# coilcube.net
KiCad netlist of a schematic drawn in EAGLE
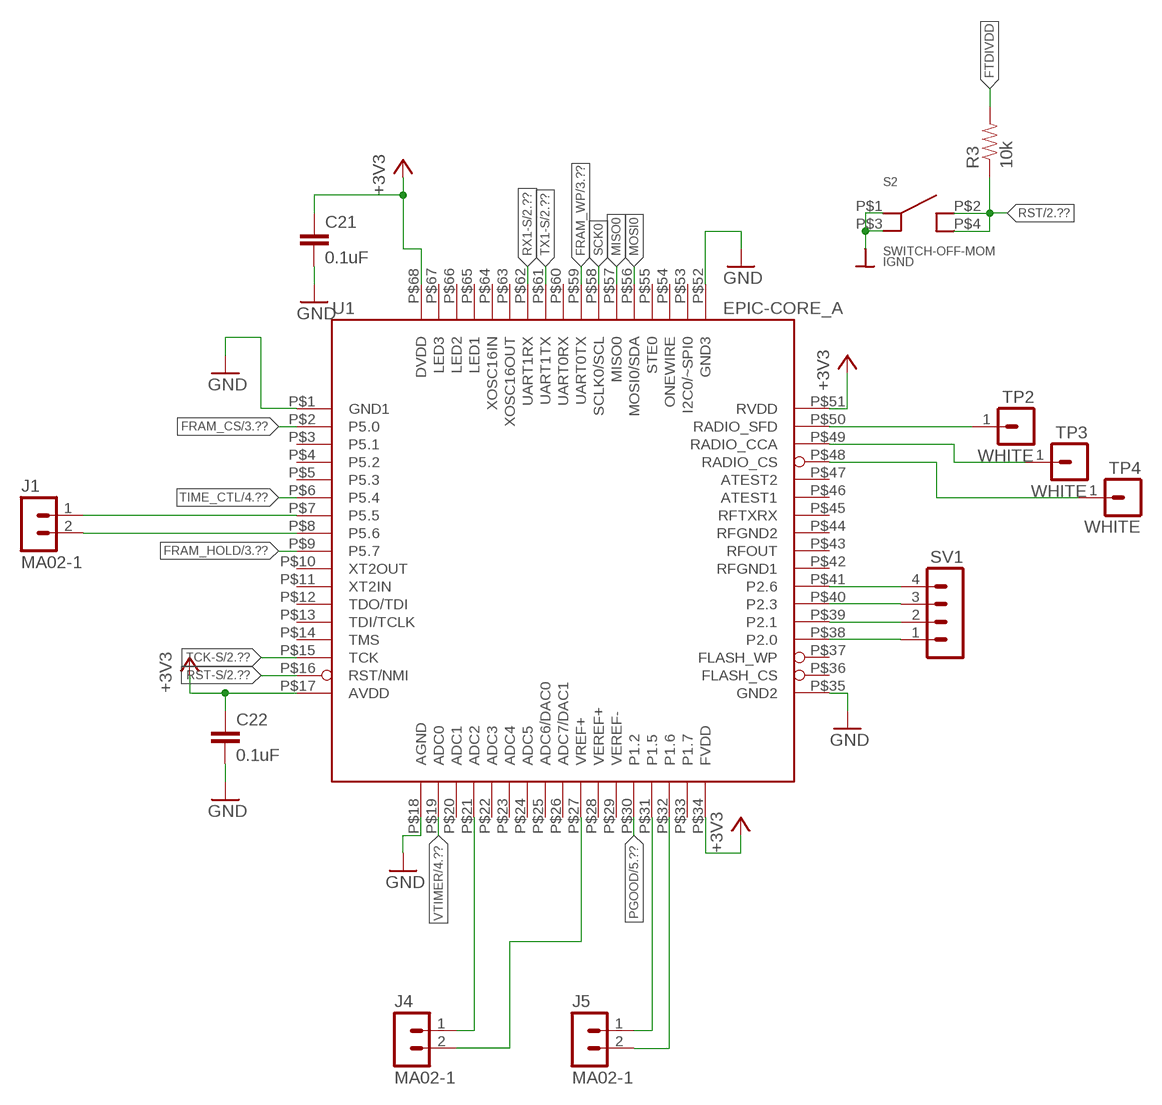
[diagram p0: schematic, sheet 1]
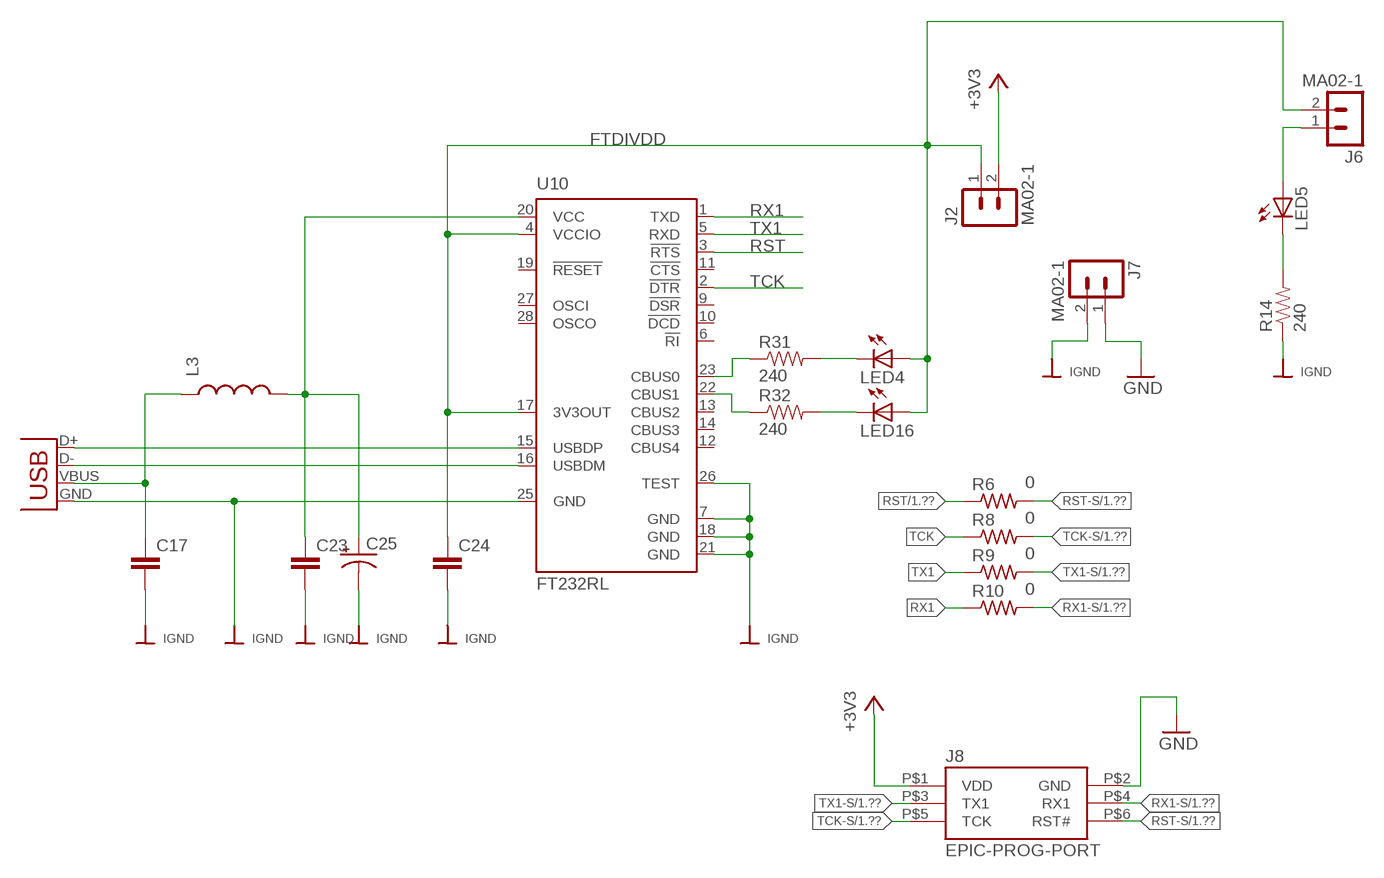
[diagram p1: schematic, sheet 2]
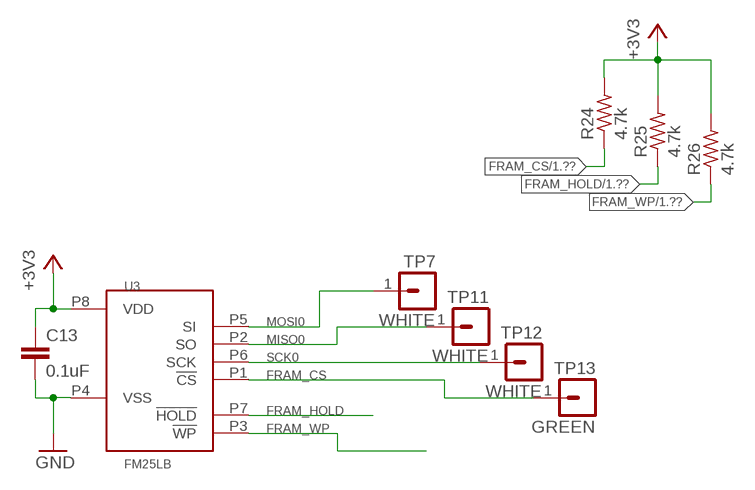
[diagram p2: schematic, sheet 3]
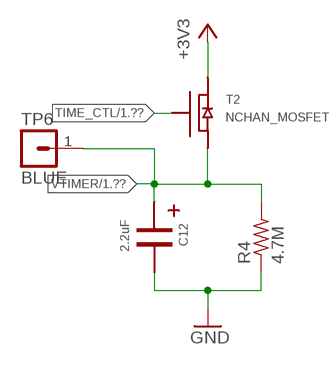
[diagram p3: schematic, sheet 4]
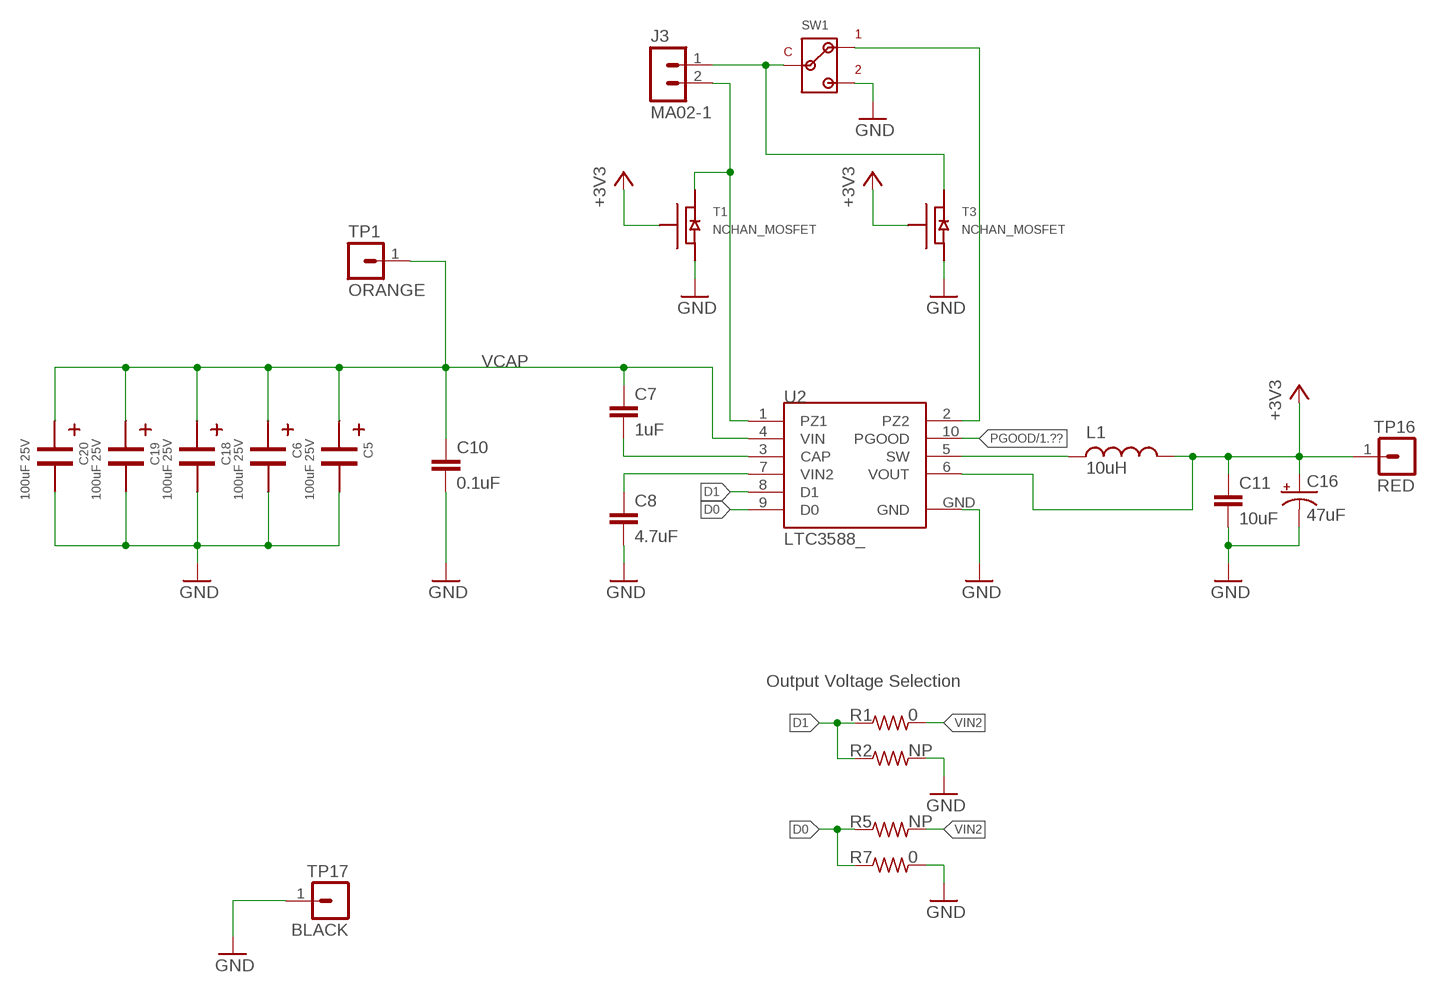
[diagram p4: schematic, sheet 5]

(export (version "E")
  (design (tool "Eeschema 10.0.6"))
  (components
    (comp (ref "C17")
      (value "CAP0603-CAP")
      (footprint "eagle-import:0603-CAP")
      (libsource (lib "eagle-import") (part "CAP0603-CAP"))
    )
    (comp (ref "C23")
      (value "CAP0603-CAP")
      (footprint "eagle-import:0603-CAP")
      (libsource (lib "eagle-import") (part "CAP0603-CAP"))
    )
    (comp (ref "C24")
      (value "CAP0603-CAP")
      (footprint "eagle-import:0603-CAP")
      (libsource (lib "eagle-import") (part "CAP0603-CAP"))
    )
    (comp (ref "C25")
      (value "CAP_POL1206")
      (footprint "eagle-import:EIA3216")
      (libsource (lib "eagle-import") (part "CAP_POL1206"))
    )
    (comp (ref "J2")
      (value "MA02-1")
      (footprint "eagle-import:MA02-1")
      (libsource (lib "eagle-import") (part "MA02-1"))
    )
    (comp (ref "J6")
      (value "MA02-1")
      (footprint "eagle-import:MA02-1")
      (libsource (lib "eagle-import") (part "MA02-1"))
    )
    (comp (ref "J7")
      (value "MA02-1")
      (footprint "eagle-import:MA02-1")
      (libsource (lib "eagle-import") (part "MA02-1"))
    )
    (comp (ref "J8")
      (value "EPIC-PROG-PORT")
      (footprint "eagle-import:HEADER2X3X2MM")
      (libsource (lib "eagle-import") (part "EPIC-PROG-PORT"))
    )
    (comp (ref "L3")
      (value "INDUCTOR0603")
      (footprint "eagle-import:0603")
      (libsource (lib "eagle-import") (part "INDUCTOR0603"))
    )
    (comp (ref "LED4")
      (value "LED0603")
      (footprint "eagle-import:LED-0603")
      (libsource (lib "eagle-import") (part "LED0603"))
    )
    (comp (ref "LED5")
      (value "LED0603")
      (footprint "eagle-import:LED-0603")
      (libsource (lib "eagle-import") (part "LED0603"))
    )
    (comp (ref "LED16")
      (value "LED0603")
      (footprint "eagle-import:LED-0603")
      (libsource (lib "eagle-import") (part "LED0603"))
    )
    (comp (ref "R6")
      (value "0")
      (footprint "eagle-import:R0603")
      (libsource (lib "eagle-import") (part "R-US_R0603"))
    )
    (comp (ref "R8")
      (value "0")
      (footprint "eagle-import:R0603")
      (libsource (lib "eagle-import") (part "R-US_R0603"))
    )
    (comp (ref "R9")
      (value "0")
      (footprint "eagle-import:R0603")
      (libsource (lib "eagle-import") (part "R-US_R0603"))
    )
    (comp (ref "R10")
      (value "0")
      (footprint "eagle-import:R0603")
      (libsource (lib "eagle-import") (part "R-US_R0603"))
    )
    (comp (ref "R14")
      (value "240")
      (footprint "eagle-import:0603-RES")
      (libsource (lib "eagle-import") (part "RESISTOR0603-RES"))
    )
    (comp (ref "R31")
      (value "240")
      (footprint "eagle-import:0603-RES")
      (libsource (lib "eagle-import") (part "RESISTOR0603-RES"))
    )
    (comp (ref "R32")
      (value "240")
      (footprint "eagle-import:0603-RES")
      (libsource (lib "eagle-import") (part "RESISTOR0603-RES"))
    )
    (comp (ref "U10")
      (value "FT232RL")
      (footprint "eagle-import:SSOP28")
      (libsource (lib "eagle-import") (part "FT232RL"))
    )
    (comp (ref "X2")
      (value "USBSMD")
      (footprint "eagle-import:USB-MINIB")
      (libsource (lib "eagle-import") (part "USBSMD"))
    )
    (comp (ref "C5")
      (value "100uF 25V")
      (footprint "eagle-import:2917_CAP_POL")
      (libsource (lib "eagle-import") (part "2917_CAP_POL"))
    )
    (comp (ref "C6")
      (value "100uF 25V")
      (footprint "eagle-import:2917_CAP_POL")
      (libsource (lib "eagle-import") (part "2917_CAP_POL"))
    )
    (comp (ref "C7")
      (value "1uF")
      (footprint "eagle-import:C0603")
      (libsource (lib "eagle-import") (part "C-EUC0603"))
    )
    (comp (ref "C8")
      (value "4.7uF")
      (footprint "eagle-import:C0603")
      (libsource (lib "eagle-import") (part "C-EUC0603"))
    )
    (comp (ref "C10")
      (value "0.1uF")
      (footprint "eagle-import:C0603")
      (libsource (lib "eagle-import") (part "C-EUC0603"))
    )
    (comp (ref "C11")
      (value "10uF")
      (footprint "eagle-import:C1206")
      (libsource (lib "eagle-import") (part "C-EUC1206"))
    )
    (comp (ref "C16")
      (value "47uF")
      (footprint "eagle-import:EIA3216")
      (libsource (lib "eagle-import") (part "SparkFun-Passives_CAP_POL1206"))
    )
    (comp (ref "C18")
      (value "100uF 25V")
      (footprint "eagle-import:2917_CAP_POL")
      (libsource (lib "eagle-import") (part "2917_CAP_POL"))
    )
    (comp (ref "C19")
      (value "100uF 25V")
      (footprint "eagle-import:2917_CAP_POL")
      (libsource (lib "eagle-import") (part "2917_CAP_POL"))
    )
    (comp (ref "C20")
      (value "100uF 25V")
      (footprint "eagle-import:2917_CAP_POL")
      (libsource (lib "eagle-import") (part "2917_CAP_POL"))
    )
    (comp (ref "J3")
      (value "MA02-1")
      (footprint "eagle-import:MA02-1")
      (libsource (lib "eagle-import") (part "MA02-1"))
    )
    (comp (ref "L1")
      (value "10uH")
      (footprint "eagle-import:1210")
      (libsource (lib "eagle-import") (part "SparkFun-Passives_INDUCTOR1210"))
    )
    (comp (ref "R1")
      (value "0")
      (footprint "eagle-import:R0603")
      (libsource (lib "eagle-import") (part "R-US_R0603"))
    )
    (comp (ref "R2")
      (value "NP")
      (footprint "eagle-import:R0603")
      (libsource (lib "eagle-import") (part "R-US_R0603"))
    )
    (comp (ref "R5")
      (value "NP")
      (footprint "eagle-import:R0603")
      (libsource (lib "eagle-import") (part "R-US_R0603"))
    )
    (comp (ref "R7")
      (value "0")
      (footprint "eagle-import:R0603")
      (libsource (lib "eagle-import") (part "R-US_R0603"))
    )
    (comp (ref "SW1")
      (value "SWITCH_SPDP")
      (footprint "eagle-import:SWITCH_SPDP")
      (libsource (lib "eagle-import") (part "SWITCH_SPDP"))
    )
    (comp (ref "T1")
      (value "NCHAN_MOSFET")
      (footprint "eagle-import:NCHAN_MOSFET")
      (libsource (lib "eagle-import") (part "NCHAN_MOSFET"))
    )
    (comp (ref "T3")
      (value "NCHAN_MOSFET")
      (footprint "eagle-import:NCHAN_MOSFET")
      (libsource (lib "eagle-import") (part "NCHAN_MOSFET"))
    )
    (comp (ref "TP1")
      (value "ORANGE")
      (footprint "eagle-import:MA01-1")
      (libsource (lib "eagle-import") (part "MA01-1"))
    )
    (comp (ref "TP16")
      (value "RED")
      (footprint "eagle-import:MA01-1")
      (libsource (lib "eagle-import") (part "MA01-1"))
    )
    (comp (ref "TP17")
      (value "BLACK")
      (footprint "eagle-import:MA01-1")
      (libsource (lib "eagle-import") (part "MA01-1"))
    )
    (comp (ref "U2")
      (value "LTC3588_")
      (footprint "eagle-import:MSOP-10-GNDPAD")
      (libsource (lib "eagle-import") (part "LTC3588_"))
    )
    (comp (ref "C13")
      (value "0.1uF")
      (footprint "eagle-import:C0603")
      (libsource (lib "eagle-import") (part "C-EUC0603"))
    )
    (comp (ref "R24")
      (value "4.7k")
      (footprint "eagle-import:R0603")
      (libsource (lib "eagle-import") (part "R-US_R0603"))
    )
    (comp (ref "R25")
      (value "4.7k")
      (footprint "eagle-import:R0603")
      (libsource (lib "eagle-import") (part "R-US_R0603"))
    )
    (comp (ref "R26")
      (value "4.7k")
      (footprint "eagle-import:R0603")
      (libsource (lib "eagle-import") (part "R-US_R0603"))
    )
    (comp (ref "TP7")
      (value "WHITE")
      (footprint "eagle-import:MA01-1")
      (libsource (lib "eagle-import") (part "MA01-1"))
    )
    (comp (ref "TP11")
      (value "WHITE")
      (footprint "eagle-import:MA01-1")
      (libsource (lib "eagle-import") (part "MA01-1"))
    )
    (comp (ref "TP12")
      (value "WHITE")
      (footprint "eagle-import:MA01-1")
      (libsource (lib "eagle-import") (part "MA01-1"))
    )
    (comp (ref "TP13")
      (value "GREEN")
      (footprint "eagle-import:MA01-1")
      (libsource (lib "eagle-import") (part "MA01-1"))
    )
    (comp (ref "U3")
      (value "FM25LB")
      (footprint "eagle-import:SOIC_8")
      (libsource (lib "eagle-import") (part "FM25LB"))
    )
    (comp (ref "C21")
      (value "0.1uF")
      (footprint "eagle-import:C0603")
      (libsource (lib "eagle-import") (part "C-EUC0603"))
    )
    (comp (ref "C22")
      (value "0.1uF")
      (footprint "eagle-import:C0603")
      (libsource (lib "eagle-import") (part "C-EUC0603"))
    )
    (comp (ref "J1")
      (value "MA02-1")
      (footprint "eagle-import:MA02-1")
      (libsource (lib "eagle-import") (part "MA02-1"))
    )
    (comp (ref "J4")
      (value "MA02-1")
      (footprint "eagle-import:MA02-1")
      (libsource (lib "eagle-import") (part "MA02-1"))
    )
    (comp (ref "J5")
      (value "MA02-1")
      (footprint "eagle-import:MA02-1")
      (libsource (lib "eagle-import") (part "MA02-1"))
    )
    (comp (ref "R3")
      (value "10k")
      (footprint "eagle-import:0603-RES")
      (libsource (lib "eagle-import") (part "RESISTOR0603-RES"))
    )
    (comp (ref "S2")
      (value "SWITCH-OFF-MOM")
      (footprint "eagle-import:SWITCH-OFF-MOM")
      (libsource (lib "eagle-import") (part "SWITCH-OFF-MOM"))
    )
    (comp (ref "SV1")
      (value "MA04-1")
      (footprint "eagle-import:MA04-1")
      (libsource (lib "eagle-import") (part "MA04-1"))
    )
    (comp (ref "TP2")
      (value "WHITE")
      (footprint "eagle-import:MA01-1")
      (libsource (lib "eagle-import") (part "MA01-1"))
    )
    (comp (ref "TP3")
      (value "WHITE")
      (footprint "eagle-import:MA01-1")
      (libsource (lib "eagle-import") (part "MA01-1"))
    )
    (comp (ref "TP4")
      (value "WHITE")
      (footprint "eagle-import:MA01-1")
      (libsource (lib "eagle-import") (part "MA01-1"))
    )
    (comp (ref "U1")
      (value "EPIC-CORE_A")
      (footprint "eagle-import:EPIC-LCC68")
      (libsource (lib "eagle-import") (part "EPIC-CORE_A"))
    )
    (comp (ref "C12")
      (value "2.2uF")
      (footprint "eagle-import:CPOL_EEA_1MM5")
      (libsource (lib "eagle-import") (part "CAP_POLEA1MM5"))
    )
    (comp (ref "R4")
      (value "4.7M")
      (footprint "eagle-import:R0805")
      (libsource (lib "eagle-import") (part "R-US_R0805"))
    )
    (comp (ref "T2")
      (value "NCHAN_MOSFET")
      (footprint "eagle-import:NCHAN_MOSFET")
      (libsource (lib "eagle-import") (part "NCHAN_MOSFET"))
    )
    (comp (ref "TP6")
      (value "BLUE")
      (footprint "eagle-import:MA01-1")
      (libsource (lib "eagle-import") (part "MA01-1"))
    )
  )
  (nets
    (net (code "1") (name "+3V3") (class "Default")
      (node (ref "C11") (pin "1") (pinfunction "1_1") (pintype "passive"))
      (node (ref "C13") (pin "1") (pinfunction "1_1") (pintype "passive"))
      (node (ref "C16") (pin "A") (pinfunction "+_A") (pintype "passive"))
      (node (ref "C21") (pin "1") (pinfunction "1_1") (pintype "passive"))
      (node (ref "C22") (pin "1") (pinfunction "1_1") (pintype "passive"))
      (node (ref "J2") (pin "2") (pinfunction "2_2") (pintype "passive"))
      (node (ref "J8") (pin "P$1") (pinfunction "VDD_P$1") (pintype "bidirectional"))
      (node (ref "L1") (pin "2") (pinfunction "2_2") (pintype "passive"))
      (node (ref "R24") (pin "2") (pinfunction "2_2") (pintype "passive"))
      (node (ref "R25") (pin "2") (pinfunction "2_2") (pintype "passive"))
      (node (ref "R26") (pin "2") (pinfunction "2_2") (pintype "passive"))
      (node (ref "T1") (pin "G") (pinfunction "G_G") (pintype "bidirectional"))
      (node (ref "T2") (pin "D") (pinfunction "D_D") (pintype "bidirectional"))
      (node (ref "T3") (pin "G") (pinfunction "G_G") (pintype "bidirectional"))
      (node (ref "TP16") (pin "1") (pinfunction "1_1") (pintype "passive"))
      (node (ref "U1") (pin "P$17") (pinfunction "AVDD_P$17") (pintype "bidirectional"))
      (node (ref "U1") (pin "P$34") (pinfunction "FVDD_P$34") (pintype "bidirectional"))
      (node (ref "U1") (pin "P$51") (pinfunction "RVDD_P$51") (pintype "bidirectional"))
      (node (ref "U1") (pin "P$68") (pinfunction "DVDD_P$68") (pintype "bidirectional"))
      (node (ref "U2") (pin "6") (pinfunction "VOUT_6") (pintype "bidirectional"))
      (node (ref "U3") (pin "P8") (pinfunction "VDD_P8") (pintype "bidirectional"))
    )
    (net (code "2") (name "D0") (class "Default")
      (node (ref "R5") (pin "1") (pinfunction "1_1") (pintype "passive"))
      (node (ref "R7") (pin "1") (pinfunction "1_1") (pintype "passive"))
      (node (ref "U2") (pin "9") (pinfunction "D0_9") (pintype "bidirectional"))
    )
    (net (code "3") (name "D1") (class "Default")
      (node (ref "R1") (pin "1") (pinfunction "1_1") (pintype "passive"))
      (node (ref "R2") (pin "1") (pinfunction "1_1") (pintype "passive"))
      (node (ref "U2") (pin "8") (pinfunction "D1_8") (pintype "bidirectional"))
    )
    (net (code "4") (name "FRAM_CS") (class "Default")
      (node (ref "R24") (pin "1") (pinfunction "1_1") (pintype "passive"))
      (node (ref "TP13") (pin "1") (pinfunction "1_1") (pintype "passive"))
      (node (ref "U1") (pin "P$2") (pinfunction "P5.0_P$2") (pintype "bidirectional"))
      (node (ref "U3") (pin "P1") (pinfunction "~{CS}_P1") (pintype "bidirectional"))
    )
    (net (code "5") (name "FRAM_HOLD") (class "Default")
      (node (ref "R25") (pin "1") (pinfunction "1_1") (pintype "passive"))
      (node (ref "U1") (pin "P$9") (pinfunction "P5.7_P$9") (pintype "bidirectional"))
      (node (ref "U3") (pin "P7") (pinfunction "~{HOLD}_P7") (pintype "bidirectional"))
    )
    (net (code "6") (name "FRAM_WP") (class "Default")
      (node (ref "R26") (pin "1") (pinfunction "1_1") (pintype "passive"))
      (node (ref "U1") (pin "P$59") (pinfunction "UART0TX_P$59") (pintype "bidirectional"))
      (node (ref "U3") (pin "P3") (pinfunction "~{WP}_P3") (pintype "bidirectional"))
    )
    (net (code "7") (name "FTDIVDD") (class "Default")
      (node (ref "C24") (pin "1") (pinfunction "1_1") (pintype "passive"))
      (node (ref "J2") (pin "1") (pinfunction "1_1") (pintype "passive"))
      (node (ref "J6") (pin "2") (pinfunction "2_2") (pintype "passive"))
      (node (ref "LED16") (pin "A") (pinfunction "A_A") (pintype "passive"))
      (node (ref "LED4") (pin "A") (pinfunction "A_A") (pintype "passive"))
      (node (ref "R3") (pin "2") (pinfunction "2_2") (pintype "passive"))
      (node (ref "U10") (pin "17") (pinfunction "3V3OUT_17") (pintype "output"))
      (node (ref "U10") (pin "4") (pinfunction "VCCIO_4") (pintype "power_in"))
    )
    (net (code "8") (name "GND") (class "Default")
      (node (ref "C10") (pin "2") (pinfunction "2_2") (pintype "passive"))
      (node (ref "C11") (pin "2") (pinfunction "2_2") (pintype "passive"))
      (node (ref "C12") (pin "-") (pinfunction "-_-") (pintype "bidirectional"))
      (node (ref "C13") (pin "2") (pinfunction "2_2") (pintype "passive"))
      (node (ref "C16") (pin "C") (pinfunction "-_C") (pintype "passive"))
      (node (ref "C18") (pin "-") (pinfunction "-_-") (pintype "bidirectional"))
      (node (ref "C19") (pin "-") (pinfunction "-_-") (pintype "bidirectional"))
      (node (ref "C20") (pin "-") (pinfunction "-_-") (pintype "bidirectional"))
      (node (ref "C21") (pin "2") (pinfunction "2_2") (pintype "passive"))
      (node (ref "C22") (pin "2") (pinfunction "2_2") (pintype "passive"))
      (node (ref "C5") (pin "-") (pinfunction "-_-") (pintype "bidirectional"))
      (node (ref "C6") (pin "-") (pinfunction "-_-") (pintype "bidirectional"))
      (node (ref "C8") (pin "2") (pinfunction "2_2") (pintype "passive"))
      (node (ref "J7") (pin "1") (pinfunction "1_1") (pintype "passive"))
      (node (ref "J8") (pin "P$2") (pinfunction "GND_P$2") (pintype "bidirectional"))
      (node (ref "R2") (pin "2") (pinfunction "2_2") (pintype "passive"))
      (node (ref "R4") (pin "1") (pinfunction "1_1") (pintype "passive"))
      (node (ref "R7") (pin "2") (pinfunction "2_2") (pintype "passive"))
      (node (ref "SW1") (pin "P3") (pinfunction "P2_P3") (pintype "bidirectional"))
      (node (ref "T1") (pin "S") (pinfunction "S_S") (pintype "bidirectional"))
      (node (ref "T3") (pin "S") (pinfunction "S_S") (pintype "bidirectional"))
      (node (ref "TP17") (pin "1") (pinfunction "1_1") (pintype "passive"))
      (node (ref "U1") (pin "P$1") (pinfunction "GND1_P$1") (pintype "bidirectional"))
      (node (ref "U1") (pin "P$18") (pinfunction "AGND_P$18") (pintype "bidirectional"))
      (node (ref "U1") (pin "P$35") (pinfunction "GND2_P$35") (pintype "bidirectional"))
      (node (ref "U1") (pin "P$52") (pinfunction "GND3_P$52") (pintype "bidirectional"))
      (node (ref "U2") (pin "GND") (pinfunction "GND_GND") (pintype "bidirectional"))
      (node (ref "U3") (pin "P4") (pinfunction "VSS_P4") (pintype "bidirectional"))
    )
    (net (code "9") (name "IGND") (class "Default")
      (node (ref "C17") (pin "2") (pinfunction "2_2") (pintype "passive"))
      (node (ref "C23") (pin "2") (pinfunction "2_2") (pintype "passive"))
      (node (ref "C24") (pin "2") (pinfunction "2_2") (pintype "passive"))
      (node (ref "C25") (pin "C") (pinfunction "-_C") (pintype "passive"))
      (node (ref "J7") (pin "2") (pinfunction "2_2") (pintype "passive"))
      (node (ref "R14") (pin "1") (pinfunction "1_1") (pintype "passive"))
      (node (ref "S2") (pin "P$1") (pinfunction "P1_P$1") (pintype "bidirectional"))
      (node (ref "S2") (pin "P$3") (pinfunction "P3_P$3") (pintype "bidirectional"))
      (node (ref "U10") (pin "18") (pinfunction "GND_18") (pintype "power_in"))
      (node (ref "U10") (pin "21") (pinfunction "GND_21") (pintype "power_in"))
      (node (ref "U10") (pin "25") (pinfunction "GND_25") (pintype "power_in"))
      (node (ref "U10") (pin "26") (pinfunction "TEST_26") (pintype "input"))
      (node (ref "U10") (pin "7") (pinfunction "GND_7") (pintype "power_in"))
      (node (ref "X2") (pin "GND") (pinfunction "GND_GND") (pintype "bidirectional"))
    )
    (net (code "10") (name "MISO0") (class "Default")
      (node (ref "TP11") (pin "1") (pinfunction "1_1") (pintype "passive"))
      (node (ref "U1") (pin "P$57") (pinfunction "MISO0_P$57") (pintype "bidirectional"))
      (node (ref "U3") (pin "P2") (pinfunction "SO_P2") (pintype "bidirectional"))
    )
    (net (code "11") (name "MOSI0") (class "Default")
      (node (ref "TP7") (pin "1") (pinfunction "1_1") (pintype "passive"))
      (node (ref "U1") (pin "P$56") (pinfunction "MOSI0/SDA_P$56") (pintype "bidirectional"))
      (node (ref "U3") (pin "P5") (pinfunction "SI_P5") (pintype "bidirectional"))
    )
    (net (code "12") (name "Net-(C17-Pad1)") (class "Default")
      (node (ref "C17") (pin "1") (pinfunction "1_1") (pintype "passive"))
      (node (ref "L3") (pin "1") (pinfunction "1_1") (pintype "passive"))
      (node (ref "X2") (pin "VBUS") (pinfunction "VBUS_VBUS") (pintype "bidirectional"))
    )
    (net (code "13") (name "Net-(C25-+)") (class "Default")
      (node (ref "C23") (pin "1") (pinfunction "1_1") (pintype "passive"))
      (node (ref "C25") (pin "A") (pinfunction "+_A") (pintype "passive"))
      (node (ref "L3") (pin "2") (pinfunction "2_2") (pintype "passive"))
      (node (ref "U10") (pin "20") (pinfunction "VCC_20") (pintype "power_in"))
    )
    (net (code "14") (name "Net-(J6-Pad1)") (class "Default")
      (node (ref "J6") (pin "1") (pinfunction "1_1") (pintype "passive"))
      (node (ref "LED5") (pin "A") (pinfunction "A_A") (pintype "passive"))
    )
    (net (code "15") (name "Net-(LED4-PadC)") (class "Default")
      (node (ref "LED4") (pin "C") (pinfunction "C_C") (pintype "passive"))
      (node (ref "R31") (pin "2") (pinfunction "2_2") (pintype "passive"))
    )
    (net (code "16") (name "Net-(LED5-PadC)") (class "Default")
      (node (ref "LED5") (pin "C") (pinfunction "C_C") (pintype "passive"))
      (node (ref "R14") (pin "2") (pinfunction "2_2") (pintype "passive"))
    )
    (net (code "17") (name "Net-(LED16-PadC)") (class "Default")
      (node (ref "LED16") (pin "C") (pinfunction "C_C") (pintype "passive"))
      (node (ref "R32") (pin "2") (pinfunction "2_2") (pintype "passive"))
    )
    (net (code "18") (name "Net-(SW1-PC)") (class "Default")
      (node (ref "J3") (pin "1") (pinfunction "1_1") (pintype "passive"))
      (node (ref "SW1") (pin "P2") (pinfunction "PC_P2") (pintype "bidirectional"))
      (node (ref "T3") (pin "D") (pinfunction "D_D") (pintype "bidirectional"))
    )
    (net (code "19") (name "Net-(U1-ADC2)") (class "Default")
      (node (ref "J4") (pin "1") (pinfunction "1_1") (pintype "passive"))
      (node (ref "U1") (pin "P$21") (pinfunction "ADC2_P$21") (pintype "bidirectional"))
    )
    (net (code "20") (name "Net-(U1-P1.5)") (class "Default")
      (node (ref "J5") (pin "1") (pinfunction "1_1") (pintype "passive"))
      (node (ref "U1") (pin "P$31") (pinfunction "P1.5_P$31") (pintype "bidirectional"))
    )
    (net (code "21") (name "Net-(U1-P1.6)") (class "Default")
      (node (ref "J5") (pin "2") (pinfunction "2_2") (pintype "passive"))
      (node (ref "U1") (pin "P$32") (pinfunction "P1.6_P$32") (pintype "bidirectional"))
    )
    (net (code "22") (name "Net-(U1-P2.0)") (class "Default")
      (node (ref "SV1") (pin "1") (pinfunction "1_1") (pintype "passive"))
      (node (ref "U1") (pin "P$38") (pinfunction "P2.0_P$38") (pintype "bidirectional"))
    )
    (net (code "23") (name "Net-(U1-P2.1)") (class "Default")
      (node (ref "SV1") (pin "2") (pinfunction "2_2") (pintype "passive"))
      (node (ref "U1") (pin "P$39") (pinfunction "P2.1_P$39") (pintype "bidirectional"))
    )
    (net (code "24") (name "Net-(U1-P2.3)") (class "Default")
      (node (ref "SV1") (pin "3") (pinfunction "3_3") (pintype "passive"))
      (node (ref "U1") (pin "P$40") (pinfunction "P2.3_P$40") (pintype "bidirectional"))
    )
    (net (code "25") (name "Net-(U1-P2.6)") (class "Default")
      (node (ref "SV1") (pin "4") (pinfunction "4_4") (pintype "passive"))
      (node (ref "U1") (pin "P$41") (pinfunction "P2.6_P$41") (pintype "bidirectional"))
    )
    (net (code "26") (name "Net-(U1-P5.5)") (class "Default")
      (node (ref "J1") (pin "1") (pinfunction "1_1") (pintype "passive"))
      (node (ref "U1") (pin "P$7") (pinfunction "P5.5_P$7") (pintype "bidirectional"))
    )
    (net (code "27") (name "Net-(U1-P5.6)") (class "Default")
      (node (ref "J1") (pin "2") (pinfunction "2_2") (pintype "passive"))
      (node (ref "U1") (pin "P$8") (pinfunction "P5.6_P$8") (pintype "bidirectional"))
    )
    (net (code "28") (name "Net-(U1-RADIO_CCA)") (class "Default")
      (node (ref "TP3") (pin "1") (pinfunction "1_1") (pintype "passive"))
      (node (ref "U1") (pin "P$49") (pinfunction "RADIO_CCA_P$49") (pintype "bidirectional"))
    )
    (net (code "29") (name "Net-(U1-RADIO_CS)") (class "Default")
      (node (ref "TP4") (pin "1") (pinfunction "1_1") (pintype "passive"))
      (node (ref "U1") (pin "P$48") (pinfunction "RADIO_CS_P$48") (pintype "bidirectional"))
    )
    (net (code "30") (name "Net-(U1-RADIO_SFD)") (class "Default")
      (node (ref "TP2") (pin "1") (pinfunction "1_1") (pintype "passive"))
      (node (ref "U1") (pin "P$50") (pinfunction "RADIO_SFD_P$50") (pintype "bidirectional"))
    )
    (net (code "31") (name "Net-(U1-VREF+)") (class "Default")
      (node (ref "J4") (pin "2") (pinfunction "2_2") (pintype "passive"))
      (node (ref "U1") (pin "P$27") (pinfunction "VREF+_P$27") (pintype "bidirectional"))
    )
    (net (code "32") (name "Net-(U2-CAP)") (class "Default")
      (node (ref "C7") (pin "2") (pinfunction "2_2") (pintype "passive"))
      (node (ref "U2") (pin "3") (pinfunction "CAP_3") (pintype "bidirectional"))
    )
    (net (code "33") (name "Net-(U2-PZ1)") (class "Default")
      (node (ref "J3") (pin "2") (pinfunction "2_2") (pintype "passive"))
      (node (ref "T1") (pin "D") (pinfunction "D_D") (pintype "bidirectional"))
      (node (ref "U2") (pin "1") (pinfunction "PZ1_1") (pintype "bidirectional"))
    )
    (net (code "34") (name "Net-(U2-PZ2)") (class "Default")
      (node (ref "SW1") (pin "P1") (pinfunction "P1_P1") (pintype "bidirectional"))
      (node (ref "U2") (pin "2") (pinfunction "PZ2_2") (pintype "bidirectional"))
    )
    (net (code "35") (name "Net-(U2-SW)") (class "Default")
      (node (ref "L1") (pin "1") (pinfunction "1_1") (pintype "passive"))
      (node (ref "U2") (pin "5") (pinfunction "SW_5") (pintype "bidirectional"))
    )
    (net (code "36") (name "Net-(U10-CBUS0)") (class "Default")
      (node (ref "R31") (pin "1") (pinfunction "1_1") (pintype "passive"))
      (node (ref "U10") (pin "23") (pinfunction "CBUS0_23") (pintype "bidirectional"))
    )
    (net (code "37") (name "Net-(U10-CBUS1)") (class "Default")
      (node (ref "R32") (pin "1") (pinfunction "1_1") (pintype "passive"))
      (node (ref "U10") (pin "22") (pinfunction "CBUS1_22") (pintype "bidirectional"))
    )
    (net (code "38") (name "Net-(U10-USBDM)") (class "Default")
      (node (ref "U10") (pin "16") (pinfunction "USBDM_16") (pintype "bidirectional"))
      (node (ref "X2") (pin "D-") (pinfunction "D-_D-") (pintype "bidirectional"))
    )
    (net (code "39") (name "Net-(U10-USBDP)") (class "Default")
      (node (ref "U10") (pin "15") (pinfunction "USBDP_15") (pintype "bidirectional"))
      (node (ref "X2") (pin "D+") (pinfunction "D+_D+") (pintype "bidirectional"))
    )
    (net (code "40") (name "PGOOD") (class "Default")
      (node (ref "U1") (pin "P$30") (pinfunction "P1.2_P$30") (pintype "bidirectional"))
      (node (ref "U2") (pin "10") (pinfunction "PGOOD_10") (pintype "bidirectional"))
    )
    (net (code "41") (name "RST") (class "Default")
      (node (ref "R3") (pin "1") (pinfunction "1_1") (pintype "passive"))
      (node (ref "R6") (pin "1") (pinfunction "1_1") (pintype "passive"))
      (node (ref "S2") (pin "P$2") (pinfunction "P2_P$2") (pintype "bidirectional"))
      (node (ref "S2") (pin "P$4") (pinfunction "P4_P$4") (pintype "bidirectional"))
      (node (ref "U10") (pin "3") (pinfunction "~{RTS}_3") (pintype "output"))
    )
    (net (code "42") (name "RST-S") (class "Default")
      (node (ref "J8") (pin "P$6") (pinfunction "RST#_P$6") (pintype "bidirectional"))
      (node (ref "R6") (pin "2") (pinfunction "2_2") (pintype "passive"))
      (node (ref "U1") (pin "P$16") (pinfunction "RST/NMI_P$16") (pintype "bidirectional"))
    )
    (net (code "43") (name "RX1") (class "Default")
      (node (ref "R10") (pin "1") (pinfunction "1_1") (pintype "passive"))
      (node (ref "U10") (pin "1") (pinfunction "TXD_1") (pintype "output"))
    )
    (net (code "44") (name "RX1-S") (class "Default")
      (node (ref "J8") (pin "P$4") (pinfunction "RX1_P$4") (pintype "bidirectional"))
      (node (ref "R10") (pin "2") (pinfunction "2_2") (pintype "passive"))
      (node (ref "U1") (pin "P$62") (pinfunction "UART1RX_P$62") (pintype "bidirectional"))
    )
    (net (code "45") (name "SCK0") (class "Default")
      (node (ref "TP12") (pin "1") (pinfunction "1_1") (pintype "passive"))
      (node (ref "U1") (pin "P$58") (pinfunction "SCLK0/SCL_P$58") (pintype "bidirectional"))
      (node (ref "U3") (pin "P6") (pinfunction "SCK_P6") (pintype "bidirectional"))
    )
    (net (code "46") (name "TCK") (class "Default")
      (node (ref "R8") (pin "1") (pinfunction "1_1") (pintype "passive"))
      (node (ref "U10") (pin "2") (pinfunction "~{DTR}_2") (pintype "output"))
    )
    (net (code "47") (name "TCK-S") (class "Default")
      (node (ref "J8") (pin "P$5") (pinfunction "TCK_P$5") (pintype "bidirectional"))
      (node (ref "R8") (pin "2") (pinfunction "2_2") (pintype "passive"))
      (node (ref "U1") (pin "P$15") (pinfunction "TCK_P$15") (pintype "bidirectional"))
    )
    (net (code "48") (name "TIME_CTL") (class "Default")
      (node (ref "T2") (pin "G") (pinfunction "G_G") (pintype "bidirectional"))
      (node (ref "U1") (pin "P$6") (pinfunction "P5.4_P$6") (pintype "bidirectional"))
    )
    (net (code "49") (name "TX1") (class "Default")
      (node (ref "R9") (pin "1") (pinfunction "1_1") (pintype "passive"))
      (node (ref "U10") (pin "5") (pinfunction "RXD_5") (pintype "input"))
    )
    (net (code "50") (name "TX1-S") (class "Default")
      (node (ref "J8") (pin "P$3") (pinfunction "TX1_P$3") (pintype "bidirectional"))
      (node (ref "R9") (pin "2") (pinfunction "2_2") (pintype "passive"))
      (node (ref "U1") (pin "P$61") (pinfunction "UART1TX_P$61") (pintype "bidirectional"))
    )
    (net (code "51") (name "VCAP") (class "Default")
      (node (ref "C10") (pin "1") (pinfunction "1_1") (pintype "passive"))
      (node (ref "C18") (pin "+") (pinfunction "+_+") (pintype "bidirectional"))
      (node (ref "C19") (pin "+") (pinfunction "+_+") (pintype "bidirectional"))
      (node (ref "C20") (pin "+") (pinfunction "+_+") (pintype "bidirectional"))
      (node (ref "C5") (pin "+") (pinfunction "+_+") (pintype "bidirectional"))
      (node (ref "C6") (pin "+") (pinfunction "+_+") (pintype "bidirectional"))
      (node (ref "C7") (pin "1") (pinfunction "1_1") (pintype "passive"))
      (node (ref "TP1") (pin "1") (pinfunction "1_1") (pintype "passive"))
      (node (ref "U2") (pin "4") (pinfunction "VIN_4") (pintype "bidirectional"))
    )
    (net (code "52") (name "VIN2") (class "Default")
      (node (ref "C8") (pin "1") (pinfunction "1_1") (pintype "passive"))
      (node (ref "R1") (pin "2") (pinfunction "2_2") (pintype "passive"))
      (node (ref "R5") (pin "2") (pinfunction "2_2") (pintype "passive"))
      (node (ref "U2") (pin "7") (pinfunction "VIN2_7") (pintype "bidirectional"))
    )
    (net (code "53") (name "VTIMER") (class "Default")
      (node (ref "C12") (pin "+") (pinfunction "+_+") (pintype "bidirectional"))
      (node (ref "R4") (pin "2") (pinfunction "2_2") (pintype "passive"))
      (node (ref "T2") (pin "S") (pinfunction "S_S") (pintype "bidirectional"))
      (node (ref "TP6") (pin "1") (pinfunction "1_1") (pintype "passive"))
      (node (ref "U1") (pin "P$19") (pinfunction "ADC0_P$19") (pintype "bidirectional"))
    )
    (net (code "54") (name "unconnected-(U1-ADC1-PadP$20)") (class "Default")
      (node (ref "U1") (pin "P$20") (pinfunction "ADC1_P$20") (pintype "bidirectional"))
    )
    (net (code "55") (name "unconnected-(U1-ADC3-PadP$22)") (class "Default")
      (node (ref "U1") (pin "P$22") (pinfunction "ADC3_P$22") (pintype "bidirectional"))
    )
    (net (code "56") (name "unconnected-(U1-ADC4-PadP$23)") (class "Default")
      (node (ref "U1") (pin "P$23") (pinfunction "ADC4_P$23") (pintype "bidirectional"))
    )
    (net (code "57") (name "unconnected-(U1-ADC5-PadP$24)") (class "Default")
      (node (ref "U1") (pin "P$24") (pinfunction "ADC5_P$24") (pintype "bidirectional"))
    )
    (net (code "58") (name "unconnected-(U1-ADC6{slash}DAC0-PadP$25)") (class "Default")
      (node (ref "U1") (pin "P$25") (pinfunction "ADC6/DAC0_P$25") (pintype "bidirectional"))
    )
    (net (code "59") (name "unconnected-(U1-ADC7{slash}DAC1-PadP$26)") (class "Default")
      (node (ref "U1") (pin "P$26") (pinfunction "ADC7/DAC1_P$26") (pintype "bidirectional"))
    )
    (net (code "60") (name "unconnected-(U1-ATEST1-PadP$46)") (class "Default")
      (node (ref "U1") (pin "P$46") (pinfunction "ATEST1_P$46") (pintype "bidirectional"))
    )
    (net (code "61") (name "unconnected-(U1-ATEST2-PadP$47)") (class "Default")
      (node (ref "U1") (pin "P$47") (pinfunction "ATEST2_P$47") (pintype "bidirectional"))
    )
    (net (code "62") (name "unconnected-(U1-FLASH_CS-PadP$36)") (class "Default")
      (node (ref "U1") (pin "P$36") (pinfunction "FLASH_CS_P$36") (pintype "bidirectional"))
    )
    (net (code "63") (name "unconnected-(U1-FLASH_WP-PadP$37)") (class "Default")
      (node (ref "U1") (pin "P$37") (pinfunction "FLASH_WP_P$37") (pintype "bidirectional"))
    )
    (net (code "64") (name "unconnected-(U1-I2C0{slash}~{SPI0}-PadP$53)") (class "Default")
      (node (ref "U1") (pin "P$53") (pinfunction "I2C0/~{SPI0}_P$53") (pintype "bidirectional"))
    )
    (net (code "65") (name "unconnected-(U1-LED1-PadP$65)") (class "Default")
      (node (ref "U1") (pin "P$65") (pinfunction "LED1_P$65") (pintype "bidirectional"))
    )
    (net (code "66") (name "unconnected-(U1-LED2-PadP$66)") (class "Default")
      (node (ref "U1") (pin "P$66") (pinfunction "LED2_P$66") (pintype "bidirectional"))
    )
    (net (code "67") (name "unconnected-(U1-LED3-PadP$67)") (class "Default")
      (node (ref "U1") (pin "P$67") (pinfunction "LED3_P$67") (pintype "bidirectional"))
    )
    (net (code "68") (name "unconnected-(U1-ONEWIRE-PadP$54)") (class "Default")
      (node (ref "U1") (pin "P$54") (pinfunction "ONEWIRE_P$54") (pintype "bidirectional"))
    )
    (net (code "69") (name "unconnected-(U1-P1.7-PadP$33)") (class "Default")
      (node (ref "U1") (pin "P$33") (pinfunction "P1.7_P$33") (pintype "bidirectional"))
    )
    (net (code "70") (name "unconnected-(U1-P5.1-PadP$3)") (class "Default")
      (node (ref "U1") (pin "P$3") (pinfunction "P5.1_P$3") (pintype "bidirectional"))
    )
    (net (code "71") (name "unconnected-(U1-P5.2-PadP$4)") (class "Default")
      (node (ref "U1") (pin "P$4") (pinfunction "P5.2_P$4") (pintype "bidirectional"))
    )
    (net (code "72") (name "unconnected-(U1-P5.3-PadP$5)") (class "Default")
      (node (ref "U1") (pin "P$5") (pinfunction "P5.3_P$5") (pintype "bidirectional"))
    )
    (net (code "73") (name "unconnected-(U1-RFGND1-PadP$42)") (class "Default")
      (node (ref "U1") (pin "P$42") (pinfunction "RFGND1_P$42") (pintype "bidirectional"))
    )
    (net (code "74") (name "unconnected-(U1-RFGND2-PadP$44)") (class "Default")
      (node (ref "U1") (pin "P$44") (pinfunction "RFGND2_P$44") (pintype "bidirectional"))
    )
    (net (code "75") (name "unconnected-(U1-RFOUT-PadP$43)") (class "Default")
      (node (ref "U1") (pin "P$43") (pinfunction "RFOUT_P$43") (pintype "bidirectional"))
    )
    (net (code "76") (name "unconnected-(U1-RFTXRX-PadP$45)") (class "Default")
      (node (ref "U1") (pin "P$45") (pinfunction "RFTXRX_P$45") (pintype "bidirectional"))
    )
    (net (code "77") (name "unconnected-(U1-STE0-PadP$55)") (class "Default")
      (node (ref "U1") (pin "P$55") (pinfunction "STE0_P$55") (pintype "bidirectional"))
    )
    (net (code "78") (name "unconnected-(U1-TDI{slash}TCLK-PadP$13)") (class "Default")
      (node (ref "U1") (pin "P$13") (pinfunction "TDI/TCLK_P$13") (pintype "bidirectional"))
    )
    (net (code "79") (name "unconnected-(U1-TDO{slash}TDI-PadP$12)") (class "Default")
      (node (ref "U1") (pin "P$12") (pinfunction "TDO/TDI_P$12") (pintype "bidirectional"))
    )
    (net (code "80") (name "unconnected-(U1-TMS-PadP$14)") (class "Default")
      (node (ref "U1") (pin "P$14") (pinfunction "TMS_P$14") (pintype "bidirectional"))
    )
    (net (code "81") (name "unconnected-(U1-UART0RX-PadP$60)") (class "Default")
      (node (ref "U1") (pin "P$60") (pinfunction "UART0RX_P$60") (pintype "bidirectional"))
    )
    (net (code "82") (name "unconnected-(U1-VEREF+-PadP$28)") (class "Default")
      (node (ref "U1") (pin "P$28") (pinfunction "VEREF+_P$28") (pintype "bidirectional"))
    )
    (net (code "83") (name "unconnected-(U1-VEREF--PadP$29)") (class "Default")
      (node (ref "U1") (pin "P$29") (pinfunction "VEREF-_P$29") (pintype "bidirectional"))
    )
    (net (code "84") (name "unconnected-(U1-XOSC16IN-PadP$64)") (class "Default")
      (node (ref "U1") (pin "P$64") (pinfunction "XOSC16IN_P$64") (pintype "bidirectional"))
    )
    (net (code "85") (name "unconnected-(U1-XOSC16OUT-PadP$63)") (class "Default")
      (node (ref "U1") (pin "P$63") (pinfunction "XOSC16OUT_P$63") (pintype "bidirectional"))
    )
    (net (code "86") (name "unconnected-(U1-XT2IN-PadP$11)") (class "Default")
      (node (ref "U1") (pin "P$11") (pinfunction "XT2IN_P$11") (pintype "bidirectional"))
    )
    (net (code "87") (name "unconnected-(U1-XT2OUT-PadP$10)") (class "Default")
      (node (ref "U1") (pin "P$10") (pinfunction "XT2OUT_P$10") (pintype "bidirectional"))
    )
    (net (code "88") (name "unconnected-(U10-CBUS2-Pad13)") (class "Default")
      (node (ref "U10") (pin "13") (pinfunction "CBUS2_13") (pintype "bidirectional"))
    )
    (net (code "89") (name "unconnected-(U10-CBUS3-Pad14)") (class "Default")
      (node (ref "U10") (pin "14") (pinfunction "CBUS3_14") (pintype "bidirectional"))
    )
    (net (code "90") (name "unconnected-(U10-CBUS4-Pad12)") (class "Default")
      (node (ref "U10") (pin "12") (pinfunction "CBUS4_12") (pintype "bidirectional"))
    )
    (net (code "91") (name "unconnected-(U10-OSCI-Pad27)") (class "Default")
      (node (ref "U10") (pin "27") (pinfunction "OSCI_27") (pintype "input"))
    )
    (net (code "92") (name "unconnected-(U10-OSCO-Pad28)") (class "Default")
      (node (ref "U10") (pin "28") (pinfunction "OSCO_28") (pintype "output"))
    )
    (net (code "93") (name "unconnected-(U10-~{CTS}-Pad11)") (class "Default")
      (node (ref "U10") (pin "11") (pinfunction "~{CTS}_11") (pintype "input"))
    )
    (net (code "94") (name "unconnected-(U10-~{DCD}-Pad10)") (class "Default")
      (node (ref "U10") (pin "10") (pinfunction "~{DCD}_10") (pintype "input"))
    )
    (net (code "95") (name "unconnected-(U10-~{DSR}-Pad9)") (class "Default")
      (node (ref "U10") (pin "9") (pinfunction "~{DSR}_9") (pintype "input"))
    )
    (net (code "96") (name "unconnected-(U10-~{RESET}-Pad19)") (class "Default")
      (node (ref "U10") (pin "19") (pinfunction "~{RESET}_19") (pintype "input"))
    )
    (net (code "97") (name "unconnected-(U10-~{RI}-Pad6)") (class "Default")
      (node (ref "U10") (pin "6") (pinfunction "~{RI}_6") (pintype "input"))
    )
  )
)
